# 1_3_0_Power_board.net
KiCad netlist of a schematic drawn in Altium Designer
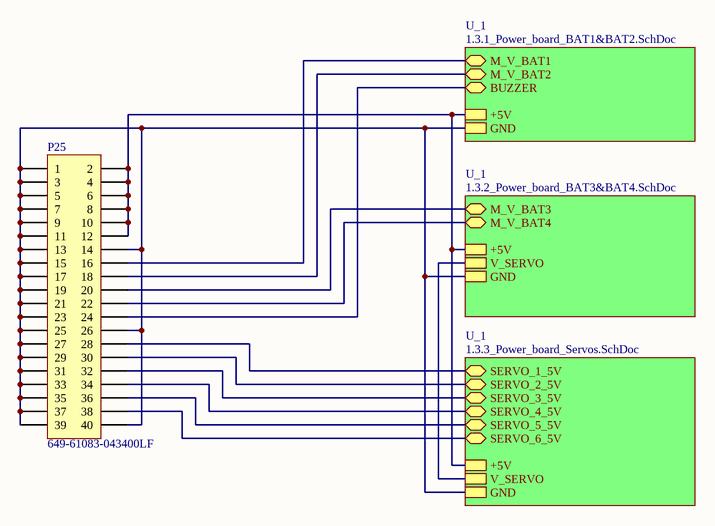
[diagram p0: 1.3.0_Power_board.SchDoc]

(export (version "E")
  (design (tool "Eeschema 10.0.6"))
  (components
    (comp (ref "P25")
      (value "61083-043400LF")
      (footprint "61083-043400LF")
      (description "Connecteurs carte à carte et mezzanine PLUG 40P")
      (fields (field (name "SUPPLIER PART NUMBER 1") "649-61083-043400LF"))
      (libsource (lib "Rocket_library") (part "61083-043400LF"))
    )
  )
  (nets
    (net (code "1") (name "/+5V") (class "Default")
      (node (ref "P25") (pin "10") (pinfunction "10_10") (pintype "passive"))
      (node (ref "P25") (pin "12") (pinfunction "12_12") (pintype "passive"))
      (node (ref "P25") (pin "2") (pinfunction "2_2") (pintype "passive"))
      (node (ref "P25") (pin "4") (pinfunction "4_4") (pintype "passive"))
      (node (ref "P25") (pin "6") (pinfunction "6_6") (pintype "passive"))
      (node (ref "P25") (pin "8") (pinfunction "8_8") (pintype "passive"))
    )
    (net (code "2") (name "/BUZZER") (class "Default")
      (node (ref "P25") (pin "24") (pinfunction "24_24") (pintype "passive"))
    )
    (net (code "3") (name "/GND") (class "Default")
      (node (ref "P25") (pin "1") (pinfunction "1_1") (pintype "passive"))
      (node (ref "P25") (pin "11") (pinfunction "11_11") (pintype "passive"))
      (node (ref "P25") (pin "13") (pinfunction "13_13") (pintype "passive"))
      (node (ref "P25") (pin "14") (pinfunction "14_14") (pintype "passive"))
      (node (ref "P25") (pin "15") (pinfunction "15_15") (pintype "passive"))
      (node (ref "P25") (pin "17") (pinfunction "17_17") (pintype "passive"))
      (node (ref "P25") (pin "19") (pinfunction "19_19") (pintype "passive"))
      (node (ref "P25") (pin "21") (pinfunction "21_21") (pintype "passive"))
      (node (ref "P25") (pin "23") (pinfunction "23_23") (pintype "passive"))
      (node (ref "P25") (pin "25") (pinfunction "25_25") (pintype "passive"))
      (node (ref "P25") (pin "26") (pinfunction "26_26") (pintype "passive"))
      (node (ref "P25") (pin "27") (pinfunction "27_27") (pintype "passive"))
      (node (ref "P25") (pin "29") (pinfunction "29_29") (pintype "passive"))
      (node (ref "P25") (pin "3") (pinfunction "3_3") (pintype "passive"))
      (node (ref "P25") (pin "31") (pinfunction "31_31") (pintype "passive"))
      (node (ref "P25") (pin "33") (pinfunction "33_33") (pintype "passive"))
      (node (ref "P25") (pin "35") (pinfunction "35_35") (pintype "passive"))
      (node (ref "P25") (pin "37") (pinfunction "37_37") (pintype "passive"))
      (node (ref "P25") (pin "39") (pinfunction "39_39") (pintype "passive"))
      (node (ref "P25") (pin "40") (pinfunction "40_40") (pintype "passive"))
      (node (ref "P25") (pin "5") (pinfunction "5_5") (pintype "passive"))
      (node (ref "P25") (pin "7") (pinfunction "7_7") (pintype "passive"))
      (node (ref "P25") (pin "9") (pinfunction "9_9") (pintype "passive"))
    )
    (net (code "4") (name "/M_V_BAT1") (class "Default")
      (node (ref "P25") (pin "16") (pinfunction "16_16") (pintype "passive"))
    )
    (net (code "5") (name "/M_V_BAT2") (class "Default")
      (node (ref "P25") (pin "18") (pinfunction "18_18") (pintype "passive"))
    )
    (net (code "6") (name "/M_V_BAT3") (class "Default")
      (node (ref "P25") (pin "20") (pinfunction "20_20") (pintype "passive"))
    )
    (net (code "7") (name "/M_V_BAT4") (class "Default")
      (node (ref "P25") (pin "22") (pinfunction "22_22") (pintype "passive"))
    )
    (net (code "8") (name "/SERVO_1_5V") (class "Default")
      (node (ref "P25") (pin "28") (pinfunction "28_28") (pintype "passive"))
    )
    (net (code "9") (name "/SERVO_2_5V") (class "Default")
      (node (ref "P25") (pin "30") (pinfunction "30_30") (pintype "passive"))
    )
    (net (code "10") (name "/SERVO_3_5V") (class "Default")
      (node (ref "P25") (pin "32") (pinfunction "32_32") (pintype "passive"))
    )
    (net (code "11") (name "/SERVO_4_5V") (class "Default")
      (node (ref "P25") (pin "34") (pinfunction "34_34") (pintype "passive"))
    )
    (net (code "12") (name "/SERVO_5_5V") (class "Default")
      (node (ref "P25") (pin "36") (pinfunction "36_36") (pintype "passive"))
    )
    (net (code "13") (name "/SERVO_6_5V") (class "Default")
      (node (ref "P25") (pin "38") (pinfunction "38_38") (pintype "passive"))
    )
  )
)
